# 4520_divider.net
KiCad netlist of a schematic drawn in EAGLE
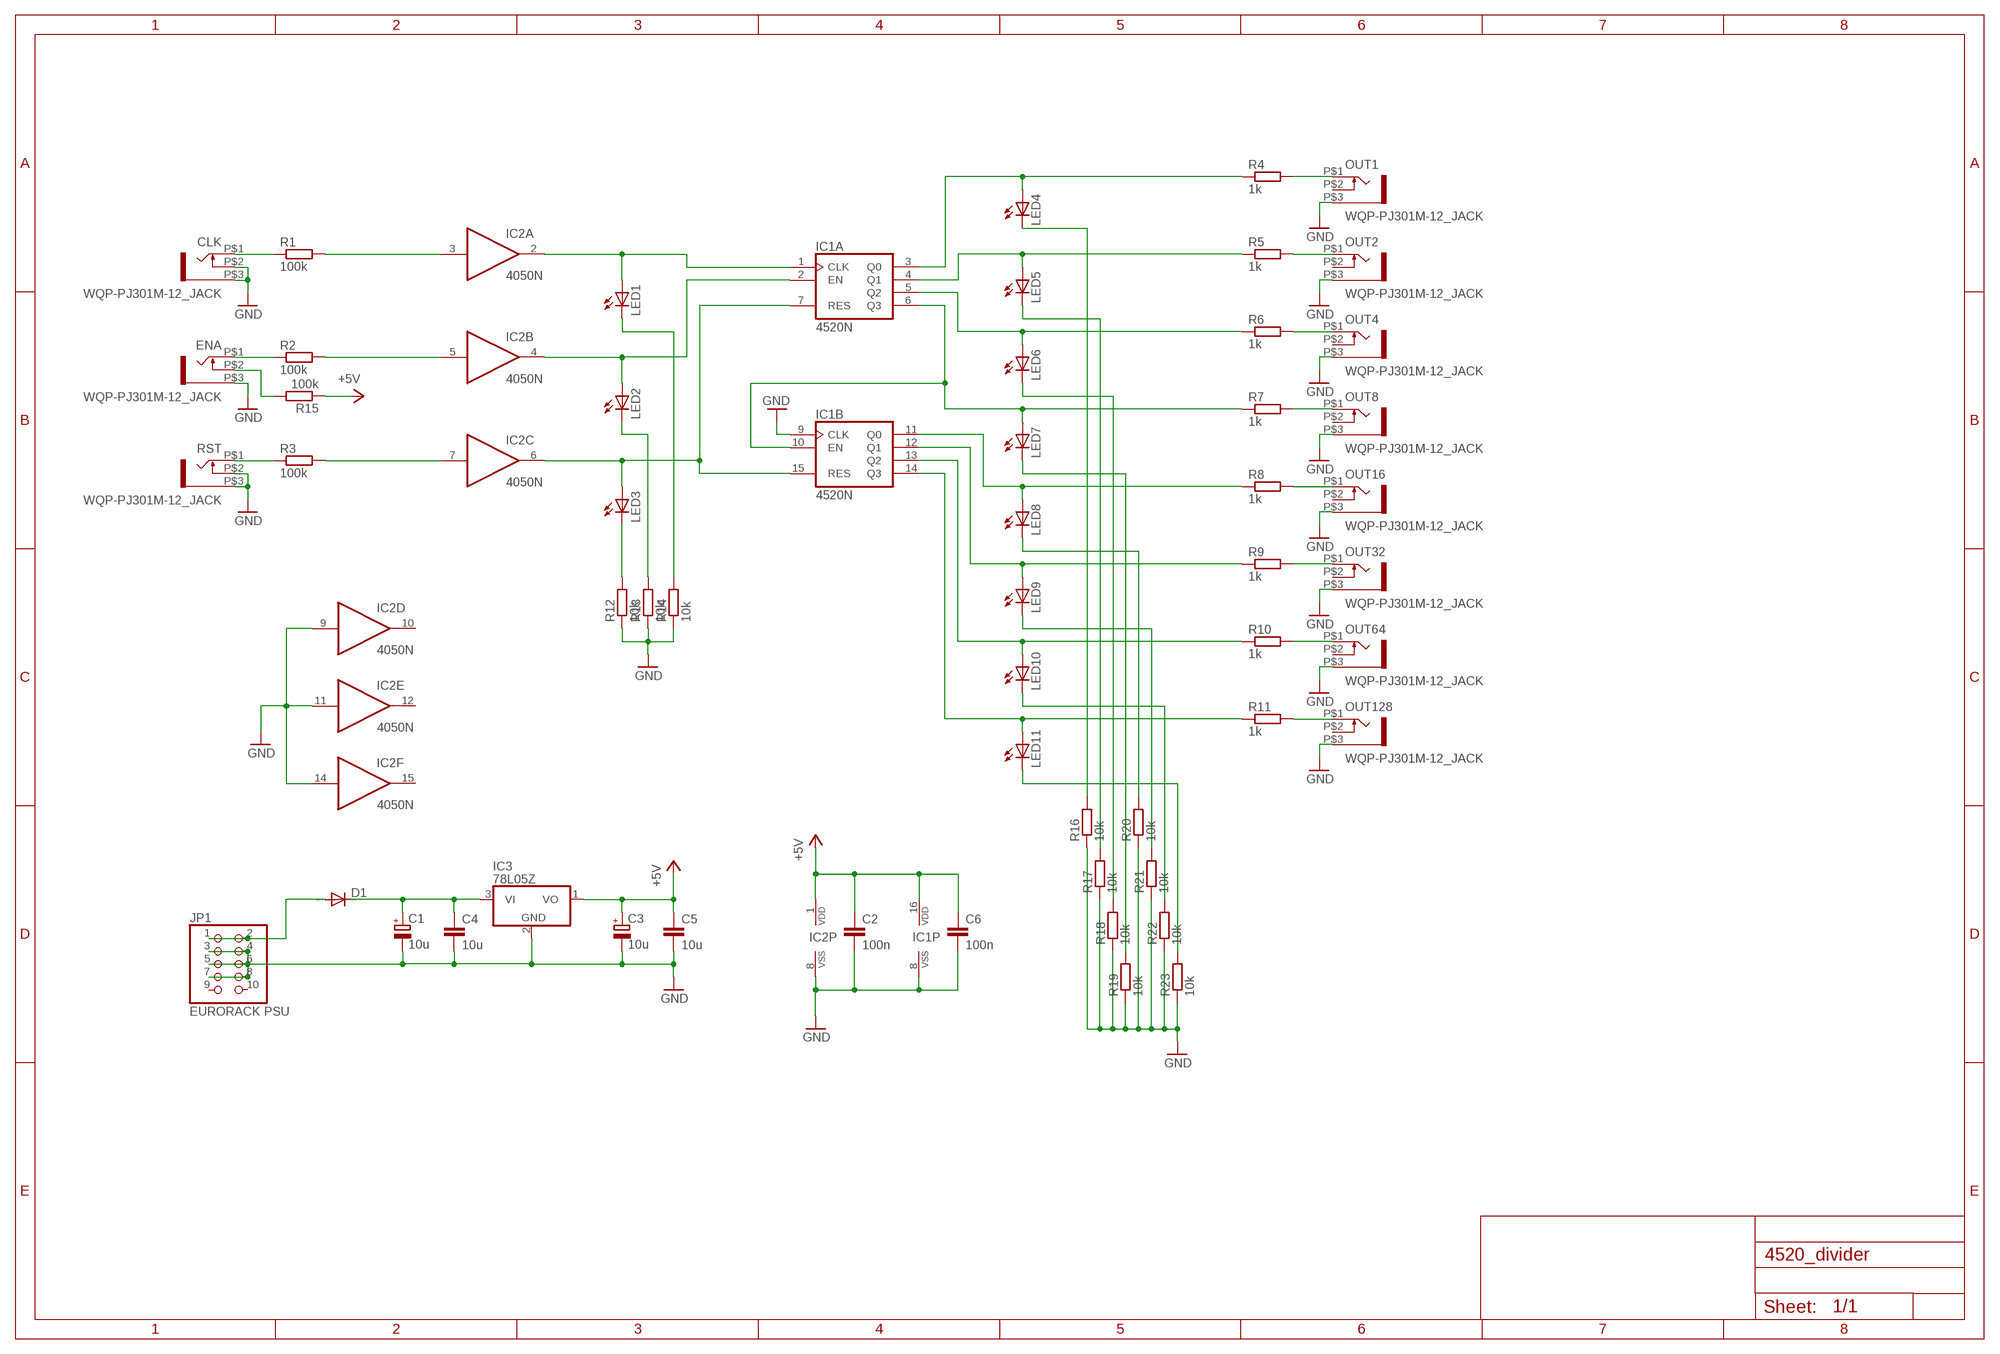
[diagram p0: schematic, sheet 1]

(export (version "E")
  (design (tool "Eeschema 10.0.6"))
  (components
    (comp (ref "C1")
      (value "10u")
      (footprint "eagle-import:E2,5-5")
      (libsource (lib "eagle-import") (part "CPOL-EUE2.5-5"))
    )
    (comp (ref "C2")
      (value "100n")
      (footprint "eagle-import:C025-025X050")
      (libsource (lib "eagle-import") (part "C-EU025-025X050"))
    )
    (comp (ref "C3")
      (value "10u")
      (footprint "eagle-import:E2,5-5")
      (libsource (lib "eagle-import") (part "CPOL-EUE2.5-5"))
    )
    (comp (ref "C4")
      (value "10u")
      (footprint "eagle-import:C1206K")
      (libsource (lib "eagle-import") (part "C-EUC1206K"))
    )
    (comp (ref "C5")
      (value "10u")
      (footprint "eagle-import:C1206K")
      (libsource (lib "eagle-import") (part "C-EUC1206K"))
    )
    (comp (ref "C6")
      (value "100n")
      (footprint "eagle-import:C025-025X050")
      (libsource (lib "eagle-import") (part "C-EU025-025X050"))
    )
    (comp (ref "CLK")
      (value "WQP-PJ301M-12_JACK")
      (footprint "eagle-import:WQP-PJ301M-12_JACK")
      (libsource (lib "eagle-import") (part "WQP-PJ301M-12_JACK"))
    )
    (comp (ref "D1")
      (value "DIODE-D-2.5")
      (footprint "eagle-import:D-2.5")
      (libsource (lib "eagle-import") (part "DIODE-D-2.5"))
    )
    (comp (ref "ENA")
      (value "WQP-PJ301M-12_JACK")
      (footprint "eagle-import:WQP-PJ301M-12_JACK")
      (libsource (lib "eagle-import") (part "WQP-PJ301M-12_JACK"))
    )
    (comp (ref "IC1")
      (value "4520N")
      (footprint "eagle-import:DIL16")
      (libsource (lib "eagle-import") (part "4520N"))
    )
    (comp (ref "IC2")
      (value "4050N")
      (footprint "eagle-import:DIL16")
      (libsource (lib "eagle-import") (part "4050N"))
    )
    (comp (ref "IC3")
      (value "78L05Z")
      (footprint "eagle-import:TO92")
      (libsource (lib "eagle-import") (part "78ZL05"))
    )
    (comp (ref "JP1")
      (value "EURORACK PSU")
      (footprint "eagle-import:2X05")
      (libsource (lib "eagle-import") (part "PINHD-2X5"))
    )
    (comp (ref "LED1")
      (value "LED3MM")
      (footprint "eagle-import:LED3MM")
      (libsource (lib "eagle-import") (part "LED3MM"))
    )
    (comp (ref "LED2")
      (value "LED3MM")
      (footprint "eagle-import:LED3MM")
      (libsource (lib "eagle-import") (part "LED3MM"))
    )
    (comp (ref "LED3")
      (value "LED3MM")
      (footprint "eagle-import:LED3MM")
      (libsource (lib "eagle-import") (part "LED3MM"))
    )
    (comp (ref "LED4")
      (value "LED3MM")
      (footprint "eagle-import:LED3MM")
      (libsource (lib "eagle-import") (part "LED3MM"))
    )
    (comp (ref "LED5")
      (value "LED3MM")
      (footprint "eagle-import:LED3MM")
      (libsource (lib "eagle-import") (part "LED3MM"))
    )
    (comp (ref "LED6")
      (value "LED3MM")
      (footprint "eagle-import:LED3MM")
      (libsource (lib "eagle-import") (part "LED3MM"))
    )
    (comp (ref "LED7")
      (value "LED3MM")
      (footprint "eagle-import:LED3MM")
      (libsource (lib "eagle-import") (part "LED3MM"))
    )
    (comp (ref "LED8")
      (value "LED3MM")
      (footprint "eagle-import:LED3MM")
      (libsource (lib "eagle-import") (part "LED3MM"))
    )
    (comp (ref "LED9")
      (value "LED3MM")
      (footprint "eagle-import:LED3MM")
      (libsource (lib "eagle-import") (part "LED3MM"))
    )
    (comp (ref "LED10")
      (value "LED3MM")
      (footprint "eagle-import:LED3MM")
      (libsource (lib "eagle-import") (part "LED3MM"))
    )
    (comp (ref "LED11")
      (value "LED3MM")
      (footprint "eagle-import:LED3MM")
      (libsource (lib "eagle-import") (part "LED3MM"))
    )
    (comp (ref "OUT1")
      (value "WQP-PJ301M-12_JACK")
      (footprint "eagle-import:WQP-PJ301M-12_JACK")
      (libsource (lib "eagle-import") (part "WQP-PJ301M-12_JACK"))
    )
    (comp (ref "OUT2")
      (value "WQP-PJ301M-12_JACK")
      (footprint "eagle-import:WQP-PJ301M-12_JACK")
      (libsource (lib "eagle-import") (part "WQP-PJ301M-12_JACK"))
    )
    (comp (ref "OUT4")
      (value "WQP-PJ301M-12_JACK")
      (footprint "eagle-import:WQP-PJ301M-12_JACK")
      (libsource (lib "eagle-import") (part "WQP-PJ301M-12_JACK"))
    )
    (comp (ref "OUT8")
      (value "WQP-PJ301M-12_JACK")
      (footprint "eagle-import:WQP-PJ301M-12_JACK")
      (libsource (lib "eagle-import") (part "WQP-PJ301M-12_JACK"))
    )
    (comp (ref "OUT16")
      (value "WQP-PJ301M-12_JACK")
      (footprint "eagle-import:WQP-PJ301M-12_JACK")
      (libsource (lib "eagle-import") (part "WQP-PJ301M-12_JACK"))
    )
    (comp (ref "OUT32")
      (value "WQP-PJ301M-12_JACK")
      (footprint "eagle-import:WQP-PJ301M-12_JACK")
      (libsource (lib "eagle-import") (part "WQP-PJ301M-12_JACK"))
    )
    (comp (ref "OUT64")
      (value "WQP-PJ301M-12_JACK")
      (footprint "eagle-import:WQP-PJ301M-12_JACK")
      (libsource (lib "eagle-import") (part "WQP-PJ301M-12_JACK"))
    )
    (comp (ref "OUT128")
      (value "WQP-PJ301M-12_JACK")
      (footprint "eagle-import:WQP-PJ301M-12_JACK")
      (libsource (lib "eagle-import") (part "WQP-PJ301M-12_JACK"))
    )
    (comp (ref "R1")
      (value "100k")
      (footprint "eagle-import:0204V")
      (libsource (lib "eagle-import") (part "R-EU_0204/2V"))
    )
    (comp (ref "R2")
      (value "100k")
      (footprint "eagle-import:0204V")
      (libsource (lib "eagle-import") (part "R-EU_0204/2V"))
    )
    (comp (ref "R3")
      (value "100k")
      (footprint "eagle-import:0204V")
      (libsource (lib "eagle-import") (part "R-EU_0204/2V"))
    )
    (comp (ref "R4")
      (value "1k")
      (footprint "eagle-import:R1206")
      (libsource (lib "eagle-import") (part "R-EU_R1206"))
    )
    (comp (ref "R5")
      (value "1k")
      (footprint "eagle-import:R1206")
      (libsource (lib "eagle-import") (part "R-EU_R1206"))
    )
    (comp (ref "R6")
      (value "1k")
      (footprint "eagle-import:R1206")
      (libsource (lib "eagle-import") (part "R-EU_R1206"))
    )
    (comp (ref "R7")
      (value "1k")
      (footprint "eagle-import:R1206")
      (libsource (lib "eagle-import") (part "R-EU_R1206"))
    )
    (comp (ref "R8")
      (value "1k")
      (footprint "eagle-import:R1206")
      (libsource (lib "eagle-import") (part "R-EU_R1206"))
    )
    (comp (ref "R9")
      (value "1k")
      (footprint "eagle-import:R1206")
      (libsource (lib "eagle-import") (part "R-EU_R1206"))
    )
    (comp (ref "R10")
      (value "1k")
      (footprint "eagle-import:R1206")
      (libsource (lib "eagle-import") (part "R-EU_R1206"))
    )
    (comp (ref "R11")
      (value "1k")
      (footprint "eagle-import:R1206")
      (libsource (lib "eagle-import") (part "R-EU_R1206"))
    )
    (comp (ref "R12")
      (value "10k")
      (footprint "eagle-import:R1206")
      (libsource (lib "eagle-import") (part "R-EU_R1206"))
    )
    (comp (ref "R13")
      (value "10k")
      (footprint "eagle-import:R1206")
      (libsource (lib "eagle-import") (part "R-EU_R1206"))
    )
    (comp (ref "R14")
      (value "10k")
      (footprint "eagle-import:R1206")
      (libsource (lib "eagle-import") (part "R-EU_R1206"))
    )
    (comp (ref "R15")
      (value "100k")
      (footprint "eagle-import:0204V")
      (libsource (lib "eagle-import") (part "R-EU_0204/2V"))
    )
    (comp (ref "R16")
      (value "10k")
      (footprint "eagle-import:R1206")
      (libsource (lib "eagle-import") (part "R-EU_R1206"))
    )
    (comp (ref "R17")
      (value "10k")
      (footprint "eagle-import:R1206")
      (libsource (lib "eagle-import") (part "R-EU_R1206"))
    )
    (comp (ref "R18")
      (value "10k")
      (footprint "eagle-import:R1206")
      (libsource (lib "eagle-import") (part "R-EU_R1206"))
    )
    (comp (ref "R19")
      (value "10k")
      (footprint "eagle-import:R1206")
      (libsource (lib "eagle-import") (part "R-EU_R1206"))
    )
    (comp (ref "R20")
      (value "10k")
      (footprint "eagle-import:R1206")
      (libsource (lib "eagle-import") (part "R-EU_R1206"))
    )
    (comp (ref "R21")
      (value "10k")
      (footprint "eagle-import:R1206")
      (libsource (lib "eagle-import") (part "R-EU_R1206"))
    )
    (comp (ref "R22")
      (value "10k")
      (footprint "eagle-import:R1206")
      (libsource (lib "eagle-import") (part "R-EU_R1206"))
    )
    (comp (ref "R23")
      (value "10k")
      (footprint "eagle-import:R1206")
      (libsource (lib "eagle-import") (part "R-EU_R1206"))
    )
    (comp (ref "RST")
      (value "WQP-PJ301M-12_JACK")
      (footprint "eagle-import:WQP-PJ301M-12_JACK")
      (libsource (lib "eagle-import") (part "WQP-PJ301M-12_JACK"))
    )
  )
  (nets
    (net (code "1") (name "+5V") (class "Default")
      (node (ref "C2") (pin "1") (pinfunction "1_1") (pintype "passive"))
      (node (ref "C3") (pin "+") (pinfunction "+_+") (pintype "passive"))
      (node (ref "C5") (pin "1") (pinfunction "1_1") (pintype "passive"))
      (node (ref "C6") (pin "1") (pinfunction "1_1") (pintype "passive"))
      (node (ref "IC1") (pin "16") (pinfunction "VDD_16") (pintype "power_in"))
      (node (ref "IC2") (pin "1") (pinfunction "VDD_1") (pintype "power_in"))
      (node (ref "IC3") (pin "1") (pinfunction "VO_1") (pintype "passive"))
      (node (ref "R15") (pin "1") (pinfunction "1_1") (pintype "passive"))
    )
    (net (code "2") (name "GND") (class "Default")
      (node (ref "C1") (pin "-") (pinfunction "-_-") (pintype "passive"))
      (node (ref "C2") (pin "2") (pinfunction "2_2") (pintype "passive"))
      (node (ref "C3") (pin "-") (pinfunction "-_-") (pintype "passive"))
      (node (ref "C4") (pin "2") (pinfunction "2_2") (pintype "passive"))
      (node (ref "C5") (pin "2") (pinfunction "2_2") (pintype "passive"))
      (node (ref "C6") (pin "2") (pinfunction "2_2") (pintype "passive"))
      (node (ref "CLK") (pin "P$2") (pinfunction "3_P$2") (pintype "passive"))
      (node (ref "CLK") (pin "P$3") (pinfunction "1_P$3") (pintype "passive"))
      (node (ref "ENA") (pin "P$3") (pinfunction "1_P$3") (pintype "passive"))
      (node (ref "IC1") (pin "8") (pinfunction "VSS_8") (pintype "power_in"))
      (node (ref "IC1") (pin "9") (pinfunction "CLK_9") (pintype "input"))
      (node (ref "IC2") (pin "11") (pinfunction "I_11") (pintype "input"))
      (node (ref "IC2") (pin "14") (pinfunction "I_14") (pintype "input"))
      (node (ref "IC2") (pin "8") (pinfunction "VSS_8") (pintype "power_in"))
      (node (ref "IC2") (pin "9") (pinfunction "I_9") (pintype "input"))
      (node (ref "IC3") (pin "2") (pinfunction "GND_2") (pintype "passive"))
      (node (ref "JP1") (pin "3") (pinfunction "3_3") (pintype "passive"))
      (node (ref "JP1") (pin "4") (pinfunction "4_4") (pintype "passive"))
      (node (ref "JP1") (pin "5") (pinfunction "5_5") (pintype "passive"))
      (node (ref "JP1") (pin "6") (pinfunction "6_6") (pintype "passive"))
      (node (ref "JP1") (pin "7") (pinfunction "7_7") (pintype "passive"))
      (node (ref "JP1") (pin "8") (pinfunction "8_8") (pintype "passive"))
      (node (ref "OUT1") (pin "P$3") (pinfunction "1_P$3") (pintype "passive"))
      (node (ref "OUT128") (pin "P$3") (pinfunction "1_P$3") (pintype "passive"))
      (node (ref "OUT16") (pin "P$3") (pinfunction "1_P$3") (pintype "passive"))
      (node (ref "OUT2") (pin "P$3") (pinfunction "1_P$3") (pintype "passive"))
      (node (ref "OUT32") (pin "P$3") (pinfunction "1_P$3") (pintype "passive"))
      (node (ref "OUT4") (pin "P$3") (pinfunction "1_P$3") (pintype "passive"))
      (node (ref "OUT64") (pin "P$3") (pinfunction "1_P$3") (pintype "passive"))
      (node (ref "OUT8") (pin "P$3") (pinfunction "1_P$3") (pintype "passive"))
      (node (ref "R12") (pin "1") (pinfunction "1_1") (pintype "passive"))
      (node (ref "R13") (pin "1") (pinfunction "1_1") (pintype "passive"))
      (node (ref "R14") (pin "1") (pinfunction "1_1") (pintype "passive"))
      (node (ref "R16") (pin "1") (pinfunction "1_1") (pintype "passive"))
      (node (ref "R17") (pin "1") (pinfunction "1_1") (pintype "passive"))
      (node (ref "R18") (pin "1") (pinfunction "1_1") (pintype "passive"))
      (node (ref "R19") (pin "1") (pinfunction "1_1") (pintype "passive"))
      (node (ref "R20") (pin "1") (pinfunction "1_1") (pintype "passive"))
      (node (ref "R21") (pin "1") (pinfunction "1_1") (pintype "passive"))
      (node (ref "R22") (pin "1") (pinfunction "1_1") (pintype "passive"))
      (node (ref "R23") (pin "1") (pinfunction "1_1") (pintype "passive"))
      (node (ref "RST") (pin "P$2") (pinfunction "3_P$2") (pintype "passive"))
      (node (ref "RST") (pin "P$3") (pinfunction "1_P$3") (pintype "passive"))
    )
    (net (code "3") (name "Net-(CLK-2)") (class "Default")
      (node (ref "CLK") (pin "P$1") (pinfunction "2_P$1") (pintype "passive"))
      (node (ref "R1") (pin "1") (pinfunction "1_1") (pintype "passive"))
    )
    (net (code "4") (name "Net-(D1-PadA)") (class "Default")
      (node (ref "D1") (pin "A") (pinfunction "A_A") (pintype "passive"))
      (node (ref "JP1") (pin "1") (pinfunction "1_1") (pintype "passive"))
      (node (ref "JP1") (pin "2") (pinfunction "2_2") (pintype "passive"))
    )
    (net (code "5") (name "Net-(ENA-2)") (class "Default")
      (node (ref "ENA") (pin "P$1") (pinfunction "2_P$1") (pintype "passive"))
      (node (ref "R2") (pin "1") (pinfunction "1_1") (pintype "passive"))
    )
    (net (code "6") (name "Net-(ENA-3)") (class "Default")
      (node (ref "ENA") (pin "P$2") (pinfunction "3_P$2") (pintype "passive"))
      (node (ref "R15") (pin "2") (pinfunction "2_2") (pintype "passive"))
    )
    (net (code "7") (name "Net-(IC1A-CLK)") (class "Default")
      (node (ref "IC1") (pin "1") (pinfunction "CLK_1") (pintype "input"))
      (node (ref "IC2") (pin "2") (pinfunction "O_2") (pintype "output"))
      (node (ref "LED1") (pin "A") (pinfunction "A_A") (pintype "passive"))
    )
    (net (code "8") (name "Net-(IC1A-EN)") (class "Default")
      (node (ref "IC1") (pin "2") (pinfunction "EN_2") (pintype "input"))
      (node (ref "IC2") (pin "4") (pinfunction "O_4") (pintype "output"))
      (node (ref "LED2") (pin "A") (pinfunction "A_A") (pintype "passive"))
    )
    (net (code "9") (name "Net-(IC1A-Q0)") (class "Default")
      (node (ref "IC1") (pin "3") (pinfunction "Q0_3") (pintype "output"))
      (node (ref "LED4") (pin "A") (pinfunction "A_A") (pintype "passive"))
      (node (ref "R4") (pin "1") (pinfunction "1_1") (pintype "passive"))
    )
    (net (code "10") (name "Net-(IC1A-Q1)") (class "Default")
      (node (ref "IC1") (pin "4") (pinfunction "Q1_4") (pintype "output"))
      (node (ref "LED5") (pin "A") (pinfunction "A_A") (pintype "passive"))
      (node (ref "R5") (pin "1") (pinfunction "1_1") (pintype "passive"))
    )
    (net (code "11") (name "Net-(IC1A-Q2)") (class "Default")
      (node (ref "IC1") (pin "5") (pinfunction "Q2_5") (pintype "output"))
      (node (ref "LED6") (pin "A") (pinfunction "A_A") (pintype "passive"))
      (node (ref "R6") (pin "1") (pinfunction "1_1") (pintype "passive"))
    )
    (net (code "12") (name "Net-(IC1A-Q3)") (class "Default")
      (node (ref "IC1") (pin "10") (pinfunction "EN_10") (pintype "input"))
      (node (ref "IC1") (pin "6") (pinfunction "Q3_6") (pintype "output"))
      (node (ref "LED7") (pin "A") (pinfunction "A_A") (pintype "passive"))
      (node (ref "R7") (pin "1") (pinfunction "1_1") (pintype "passive"))
    )
    (net (code "13") (name "Net-(IC1A-RES)") (class "Default")
      (node (ref "IC1") (pin "15") (pinfunction "RES_15") (pintype "input"))
      (node (ref "IC1") (pin "7") (pinfunction "RES_7") (pintype "input"))
      (node (ref "IC2") (pin "6") (pinfunction "O_6") (pintype "output"))
      (node (ref "LED3") (pin "A") (pinfunction "A_A") (pintype "passive"))
    )
    (net (code "14") (name "Net-(IC1B-Q0)") (class "Default")
      (node (ref "IC1") (pin "11") (pinfunction "Q0_11") (pintype "output"))
      (node (ref "LED8") (pin "A") (pinfunction "A_A") (pintype "passive"))
      (node (ref "R8") (pin "1") (pinfunction "1_1") (pintype "passive"))
    )
    (net (code "15") (name "Net-(IC1B-Q1)") (class "Default")
      (node (ref "IC1") (pin "12") (pinfunction "Q1_12") (pintype "output"))
      (node (ref "LED9") (pin "A") (pinfunction "A_A") (pintype "passive"))
      (node (ref "R9") (pin "1") (pinfunction "1_1") (pintype "passive"))
    )
    (net (code "16") (name "Net-(IC1B-Q2)") (class "Default")
      (node (ref "IC1") (pin "13") (pinfunction "Q2_13") (pintype "output"))
      (node (ref "LED10") (pin "A") (pinfunction "A_A") (pintype "passive"))
      (node (ref "R10") (pin "1") (pinfunction "1_1") (pintype "passive"))
    )
    (net (code "17") (name "Net-(IC1B-Q3)") (class "Default")
      (node (ref "IC1") (pin "14") (pinfunction "Q3_14") (pintype "output"))
      (node (ref "LED11") (pin "A") (pinfunction "A_A") (pintype "passive"))
      (node (ref "R11") (pin "1") (pinfunction "1_1") (pintype "passive"))
    )
    (net (code "18") (name "Net-(IC2A-I)") (class "Default")
      (node (ref "IC2") (pin "3") (pinfunction "I_3") (pintype "input"))
      (node (ref "R1") (pin "2") (pinfunction "2_2") (pintype "passive"))
    )
    (net (code "19") (name "Net-(IC2B-I)") (class "Default")
      (node (ref "IC2") (pin "5") (pinfunction "I_5") (pintype "input"))
      (node (ref "R2") (pin "2") (pinfunction "2_2") (pintype "passive"))
    )
    (net (code "20") (name "Net-(IC2C-I)") (class "Default")
      (node (ref "IC2") (pin "7") (pinfunction "I_7") (pintype "input"))
      (node (ref "R3") (pin "2") (pinfunction "2_2") (pintype "passive"))
    )
    (net (code "21") (name "Net-(IC3-VI)") (class "Default")
      (node (ref "C1") (pin "+") (pinfunction "+_+") (pintype "passive"))
      (node (ref "C4") (pin "1") (pinfunction "1_1") (pintype "passive"))
      (node (ref "D1") (pin "C") (pinfunction "C_C") (pintype "passive"))
      (node (ref "IC3") (pin "3") (pinfunction "VI_3") (pintype "input"))
    )
    (net (code "22") (name "Net-(LED1-C)") (class "Default")
      (node (ref "LED1") (pin "K") (pinfunction "C_K") (pintype "passive"))
      (node (ref "R14") (pin "2") (pinfunction "2_2") (pintype "passive"))
    )
    (net (code "23") (name "Net-(LED2-C)") (class "Default")
      (node (ref "LED2") (pin "K") (pinfunction "C_K") (pintype "passive"))
      (node (ref "R13") (pin "2") (pinfunction "2_2") (pintype "passive"))
    )
    (net (code "24") (name "Net-(LED3-C)") (class "Default")
      (node (ref "LED3") (pin "K") (pinfunction "C_K") (pintype "passive"))
      (node (ref "R12") (pin "2") (pinfunction "2_2") (pintype "passive"))
    )
    (net (code "25") (name "Net-(LED4-C)") (class "Default")
      (node (ref "LED4") (pin "K") (pinfunction "C_K") (pintype "passive"))
      (node (ref "R16") (pin "2") (pinfunction "2_2") (pintype "passive"))
    )
    (net (code "26") (name "Net-(LED5-C)") (class "Default")
      (node (ref "LED5") (pin "K") (pinfunction "C_K") (pintype "passive"))
      (node (ref "R17") (pin "2") (pinfunction "2_2") (pintype "passive"))
    )
    (net (code "27") (name "Net-(LED6-C)") (class "Default")
      (node (ref "LED6") (pin "K") (pinfunction "C_K") (pintype "passive"))
      (node (ref "R18") (pin "2") (pinfunction "2_2") (pintype "passive"))
    )
    (net (code "28") (name "Net-(LED7-C)") (class "Default")
      (node (ref "LED7") (pin "K") (pinfunction "C_K") (pintype "passive"))
      (node (ref "R19") (pin "2") (pinfunction "2_2") (pintype "passive"))
    )
    (net (code "29") (name "Net-(LED8-C)") (class "Default")
      (node (ref "LED8") (pin "K") (pinfunction "C_K") (pintype "passive"))
      (node (ref "R20") (pin "2") (pinfunction "2_2") (pintype "passive"))
    )
    (net (code "30") (name "Net-(LED9-C)") (class "Default")
      (node (ref "LED9") (pin "K") (pinfunction "C_K") (pintype "passive"))
      (node (ref "R21") (pin "2") (pinfunction "2_2") (pintype "passive"))
    )
    (net (code "31") (name "Net-(LED10-C)") (class "Default")
      (node (ref "LED10") (pin "K") (pinfunction "C_K") (pintype "passive"))
      (node (ref "R22") (pin "2") (pinfunction "2_2") (pintype "passive"))
    )
    (net (code "32") (name "Net-(LED11-C)") (class "Default")
      (node (ref "LED11") (pin "K") (pinfunction "C_K") (pintype "passive"))
      (node (ref "R23") (pin "2") (pinfunction "2_2") (pintype "passive"))
    )
    (net (code "33") (name "Net-(OUT1-2)") (class "Default")
      (node (ref "OUT1") (pin "P$1") (pinfunction "2_P$1") (pintype "passive"))
      (node (ref "R4") (pin "2") (pinfunction "2_2") (pintype "passive"))
    )
    (net (code "34") (name "Net-(OUT2-2)") (class "Default")
      (node (ref "OUT2") (pin "P$1") (pinfunction "2_P$1") (pintype "passive"))
      (node (ref "R5") (pin "2") (pinfunction "2_2") (pintype "passive"))
    )
    (net (code "35") (name "Net-(OUT4-2)") (class "Default")
      (node (ref "OUT4") (pin "P$1") (pinfunction "2_P$1") (pintype "passive"))
      (node (ref "R6") (pin "2") (pinfunction "2_2") (pintype "passive"))
    )
    (net (code "36") (name "Net-(OUT8-2)") (class "Default")
      (node (ref "OUT8") (pin "P$1") (pinfunction "2_P$1") (pintype "passive"))
      (node (ref "R7") (pin "2") (pinfunction "2_2") (pintype "passive"))
    )
    (net (code "37") (name "Net-(OUT16-2)") (class "Default")
      (node (ref "OUT16") (pin "P$1") (pinfunction "2_P$1") (pintype "passive"))
      (node (ref "R8") (pin "2") (pinfunction "2_2") (pintype "passive"))
    )
    (net (code "38") (name "Net-(OUT32-2)") (class "Default")
      (node (ref "OUT32") (pin "P$1") (pinfunction "2_P$1") (pintype "passive"))
      (node (ref "R9") (pin "2") (pinfunction "2_2") (pintype "passive"))
    )
    (net (code "39") (name "Net-(OUT64-2)") (class "Default")
      (node (ref "OUT64") (pin "P$1") (pinfunction "2_P$1") (pintype "passive"))
      (node (ref "R10") (pin "2") (pinfunction "2_2") (pintype "passive"))
    )
    (net (code "40") (name "Net-(OUT128-2)") (class "Default")
      (node (ref "OUT128") (pin "P$1") (pinfunction "2_P$1") (pintype "passive"))
      (node (ref "R11") (pin "2") (pinfunction "2_2") (pintype "passive"))
    )
    (net (code "41") (name "Net-(RST-2)") (class "Default")
      (node (ref "R3") (pin "1") (pinfunction "1_1") (pintype "passive"))
      (node (ref "RST") (pin "P$1") (pinfunction "2_P$1") (pintype "passive"))
    )
    (net (code "42") (name "unconnected-(IC2D-O-Pad10)") (class "Default")
      (node (ref "IC2") (pin "10") (pinfunction "O_10") (pintype "output"))
    )
    (net (code "43") (name "unconnected-(IC2E-O-Pad12)") (class "Default")
      (node (ref "IC2") (pin "12") (pinfunction "O_12") (pintype "output"))
    )
    (net (code "44") (name "unconnected-(IC2F-O-Pad15)") (class "Default")
      (node (ref "IC2") (pin "15") (pinfunction "O_15") (pintype "output"))
    )
    (net (code "45") (name "unconnected-(JP1-Pad9)") (class "Default")
      (node (ref "JP1") (pin "9") (pinfunction "9_9") (pintype "passive"))
    )
    (net (code "46") (name "unconnected-(JP1-Pad10)") (class "Default")
      (node (ref "JP1") (pin "10") (pinfunction "10_10") (pintype "passive"))
    )
    (net (code "47") (name "unconnected-(OUT1-3-PadP$2)") (class "Default")
      (node (ref "OUT1") (pin "P$2") (pinfunction "3_P$2") (pintype "passive"))
    )
    (net (code "48") (name "unconnected-(OUT2-3-PadP$2)") (class "Default")
      (node (ref "OUT2") (pin "P$2") (pinfunction "3_P$2") (pintype "passive"))
    )
    (net (code "49") (name "unconnected-(OUT4-3-PadP$2)") (class "Default")
      (node (ref "OUT4") (pin "P$2") (pinfunction "3_P$2") (pintype "passive"))
    )
    (net (code "50") (name "unconnected-(OUT8-3-PadP$2)") (class "Default")
      (node (ref "OUT8") (pin "P$2") (pinfunction "3_P$2") (pintype "passive"))
    )
    (net (code "51") (name "unconnected-(OUT16-3-PadP$2)") (class "Default")
      (node (ref "OUT16") (pin "P$2") (pinfunction "3_P$2") (pintype "passive"))
    )
    (net (code "52") (name "unconnected-(OUT32-3-PadP$2)") (class "Default")
      (node (ref "OUT32") (pin "P$2") (pinfunction "3_P$2") (pintype "passive"))
    )
    (net (code "53") (name "unconnected-(OUT64-3-PadP$2)") (class "Default")
      (node (ref "OUT64") (pin "P$2") (pinfunction "3_P$2") (pintype "passive"))
    )
    (net (code "54") (name "unconnected-(OUT128-3-PadP$2)") (class "Default")
      (node (ref "OUT128") (pin "P$2") (pinfunction "3_P$2") (pintype "passive"))
    )
  )
)
